# AQ_Schematic.net
KiCad netlist of a schematic drawn in Altium Designer
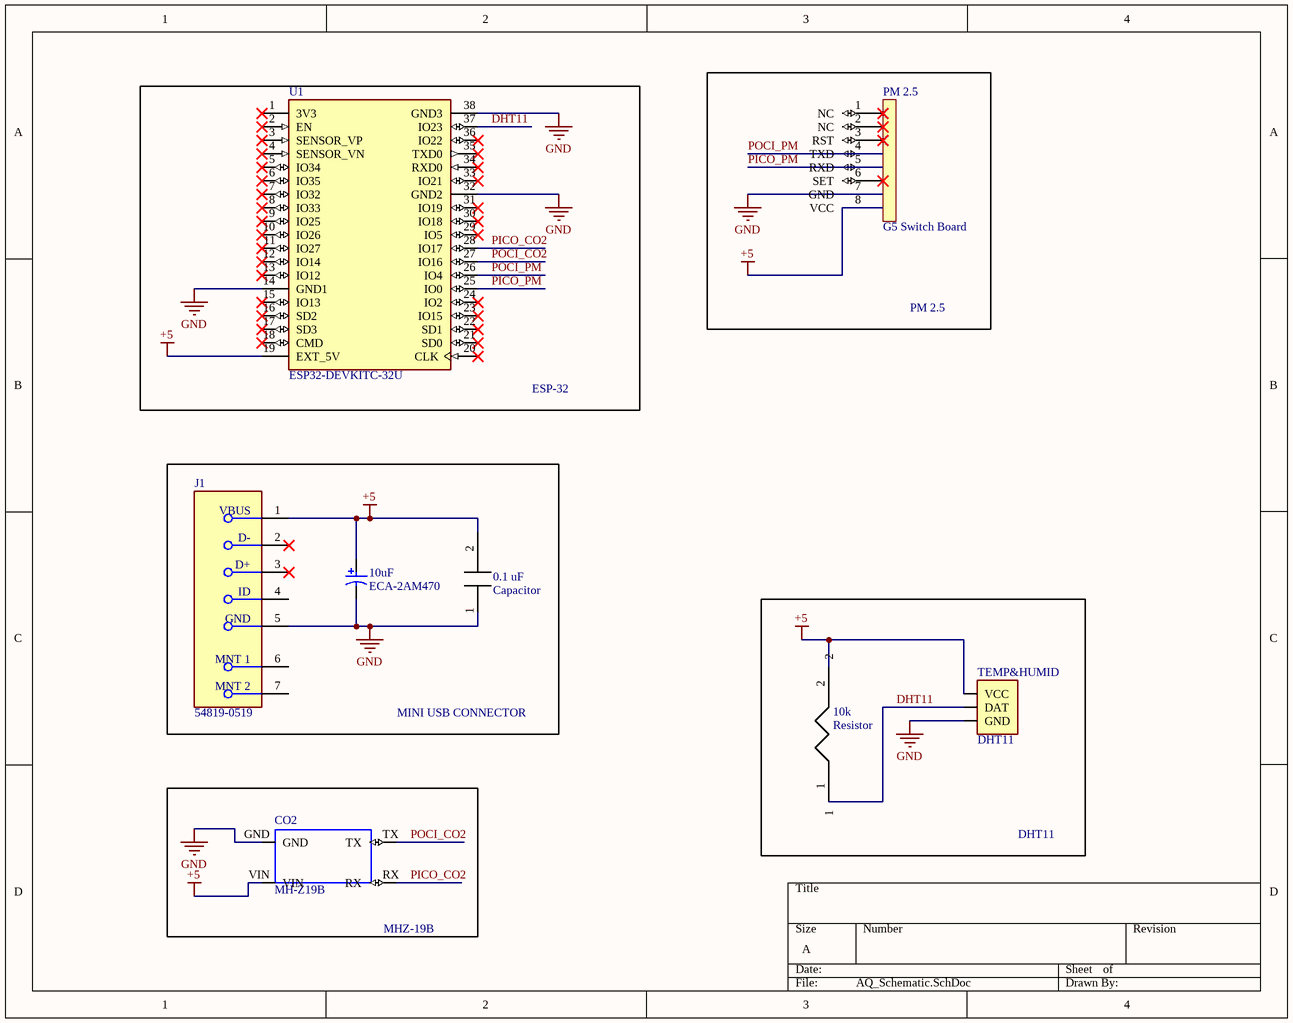
[diagram p0: AQ_Schematic.SchDoc]

(export (version "E")
  (design (tool "Eeschema 10.0.6"))
  (components
    (comp (ref "0.1 uF")
      (value "Capacitor")
      (footprint "PCBComponent_1")
      (libsource (lib "Capacitor") (part "Capacitor"))
    )
    (comp (ref "10k")
      (value "Resistor")
      (footprint "Resistor")
      (libsource (lib "Resistor") (part "Resistor"))
    )
    (comp (ref "10uF")
      (value "ECA-2AM470")
      (footprint "CAPPR65-350-1150X800X1250")
      (description "Aluminum Electrolytic Capacitor, 47 uF, +/- 20%, 100 V, -40 to 85 degC, 2-Pin THD, RoHS, Bulk")
      (libsource (lib "Components - 19.07.24 - 18.26") (part "CMP-1665-00041-1"))
    )
    (comp (ref "CO2")
      (value "MH-Z19B")
      (footprint "MH-Z19B-FOOT:MH-Z19B-FOOT")
      (description "Intelligent Infrared CO2 Module")
      (fields (field (name "MF") "Winsen"))
      (libsource (lib "MH-Z19B") (part "MH-Z19B"))
    )
    (comp (ref "J1")
      (value "54819-0519")
      (footprint "FP-54819-0519-MFG")
      (description "CONN RCPT USB2.0 MINI B 5P R/A")
      (libsource (lib "Components - 19.07.24 - 18.14") (part "CMP-04767-000009-1"))
    )
    (comp (ref "PM 2.5")
      (value "G5 Switch Board")
      (footprint "PM2.5")
      (libsource (lib "G5_Connector") (part "G5 Switch Board"))
    )
    (comp (ref "TEMP&HUMID")
      (value "DHT11")
      (footprint "SENSOR-DHT11")
      (description "Humidity, Temperature Digital Â±5% RH Through Hole")
      (fields (field (name "MF") "UNIVERSAL-SOLDER Electronics Ltd"))
      (libsource (lib "DHT11") (part "DHT11"))
    )
    (comp (ref "U1")
      (value "ESP32-DEVKITC-32U")
      (footprint "MODULE_ESP32-DEVKITC-32U")
      (fields (field (name "MF") "Espressif Systems"))
      (libsource (lib "ESP32-DEVKITC-32U") (part "ESP32-DEVKITC-32U"))
    )
  )
  (nets
    (net (code "1") (name "+5") (class "Default")
      (node (ref "10uF") (pin "1") (pinfunction "1_1") (pintype "passive"))
      (node (ref "CO2") (pin "VIN") (pinfunction "VIN_VIN") (pintype "power_in"))
      (node (ref "J1") (pin "1") (pinfunction "VBUS_1") (pintype "power_in"))
      (node (ref "PM 2.5") (pin "8") (pinfunction "VCC_8") (pintype "power_in"))
      (node (ref "TEMP&HUMID") (pin "P$1") (pinfunction "VCC_P$1") (pintype "power_in"))
      (node (ref "U1") (pin "19") (pinfunction "EXT_5V_19") (pintype "power_in"))
    )
    (net (code "2") (name "/DHT11") (class "Default")
      (node (ref "TEMP&HUMID") (pin "P$2") (pinfunction "DAT_P$2") (pintype "bidirectional"))
      (node (ref "U1") (pin "37") (pinfunction "IO23_37") (pintype "bidirectional"))
    )
    (net (code "3") (name "/PICO_CO2") (class "Default")
      (node (ref "CO2") (pin "RX") (pinfunction "RX_RX") (pintype "bidirectional"))
      (node (ref "U1") (pin "28") (pinfunction "IO17_28") (pintype "bidirectional"))
    )
    (net (code "4") (name "/PICO_PM") (class "Default")
      (node (ref "PM 2.5") (pin "5") (pinfunction "RXD_5") (pintype "bidirectional"))
      (node (ref "U1") (pin "25") (pinfunction "IO0_25") (pintype "bidirectional"))
    )
    (net (code "5") (name "/POCI_CO2") (class "Default")
      (node (ref "CO2") (pin "TX") (pinfunction "TX_TX") (pintype "bidirectional"))
      (node (ref "U1") (pin "27") (pinfunction "IO16_27") (pintype "bidirectional"))
    )
    (net (code "6") (name "/POCI_PM") (class "Default")
      (node (ref "PM 2.5") (pin "4") (pinfunction "TXD_4") (pintype "bidirectional"))
      (node (ref "U1") (pin "26") (pinfunction "IO4_26") (pintype "bidirectional"))
    )
    (net (code "7") (name "GND") (class "Default")
      (node (ref "10uF") (pin "2") (pinfunction "2_2") (pintype "passive"))
      (node (ref "CO2") (pin "GND") (pinfunction "GND_GND") (pintype "power_in"))
      (node (ref "J1") (pin "5") (pinfunction "GND_5") (pintype "power_in"))
      (node (ref "PM 2.5") (pin "7") (pinfunction "GND_7") (pintype "power_in"))
      (node (ref "TEMP&HUMID") (pin "P$4") (pinfunction "GND_P$4") (pintype "power_in"))
      (node (ref "U1") (pin "14") (pinfunction "GND1_14") (pintype "power_in"))
      (node (ref "U1") (pin "32") (pinfunction "GND2_32") (pintype "power_in"))
      (node (ref "U1") (pin "38") (pinfunction "GND3_38") (pintype "power_in"))
    )
    (net (code "8") (name "unconnected-(0.1 uF-Pad1)") (class "Default")
      (node (ref "0.1 uF") (pin "1") (pintype "passive"))
    )
    (net (code "9") (name "unconnected-(0.1 uF-Pad2)") (class "Default")
      (node (ref "0.1 uF") (pin "2") (pintype "passive"))
    )
    (net (code "10") (name "unconnected-(10k-Pad1)") (class "Default")
      (node (ref "10k") (pin "1") (pinfunction "1_1") (pintype "passive"))
    )
    (net (code "11") (name "unconnected-(10k-Pad2)") (class "Default")
      (node (ref "10k") (pin "2") (pinfunction "2_2") (pintype "passive"))
    )
    (net (code "12") (name "unconnected-(J1-D+-Pad3)") (class "Default")
      (node (ref "J1") (pin "3") (pinfunction "D+_3") (pintype "passive+no_connect"))
    )
    (net (code "13") (name "unconnected-(J1-D--Pad2)") (class "Default")
      (node (ref "J1") (pin "2") (pinfunction "D-_2") (pintype "passive+no_connect"))
    )
    (net (code "14") (name "unconnected-(J1-ID-Pad4)") (class "Default")
      (node (ref "J1") (pin "4") (pinfunction "ID_4") (pintype "passive"))
    )
    (net (code "15") (name "unconnected-(J1-MNT_1-Pad6)") (class "Default")
      (node (ref "J1") (pin "6") (pinfunction "MNT_1_6") (pintype "passive"))
    )
    (net (code "16") (name "unconnected-(J1-MNT_2-Pad7)") (class "Default")
      (node (ref "J1") (pin "7") (pinfunction "MNT_2_7") (pintype "passive"))
    )
    (net (code "17") (name "unconnected-(PM 2.5-NC-Pad1)") (class "Default")
      (node (ref "PM 2.5") (pin "1") (pinfunction "NC_1") (pintype "bidirectional+no_connect"))
    )
    (net (code "18") (name "unconnected-(PM 2.5-NC-Pad2)") (class "Default")
      (node (ref "PM 2.5") (pin "2") (pinfunction "NC_2") (pintype "bidirectional+no_connect"))
    )
    (net (code "19") (name "unconnected-(PM 2.5-RST-Pad3)") (class "Default")
      (node (ref "PM 2.5") (pin "3") (pinfunction "RST_3") (pintype "bidirectional+no_connect"))
    )
    (net (code "20") (name "unconnected-(PM 2.5-SET-Pad6)") (class "Default")
      (node (ref "PM 2.5") (pin "6") (pinfunction "SET_6") (pintype "bidirectional+no_connect"))
    )
    (net (code "21") (name "unconnected-(U1-3V3-Pad1)") (class "Default")
      (node (ref "U1") (pin "1") (pinfunction "3V3_1") (pintype "power_in+no_connect"))
    )
    (net (code "22") (name "unconnected-(U1-CLK-Pad20)") (class "Default")
      (node (ref "U1") (pin "20") (pinfunction "CLK_20") (pintype "input+no_connect"))
    )
    (net (code "23") (name "unconnected-(U1-CMD-Pad18)") (class "Default")
      (node (ref "U1") (pin "18") (pinfunction "CMD_18") (pintype "bidirectional+no_connect"))
    )
    (net (code "24") (name "unconnected-(U1-EN-Pad2)") (class "Default")
      (node (ref "U1") (pin "2") (pinfunction "EN_2") (pintype "input+no_connect"))
    )
    (net (code "25") (name "unconnected-(U1-IO2-Pad24)") (class "Default")
      (node (ref "U1") (pin "24") (pinfunction "IO2_24") (pintype "bidirectional+no_connect"))
    )
    (net (code "26") (name "unconnected-(U1-IO5-Pad29)") (class "Default")
      (node (ref "U1") (pin "29") (pinfunction "IO5_29") (pintype "bidirectional+no_connect"))
    )
    (net (code "27") (name "unconnected-(U1-IO12-Pad13)") (class "Default")
      (node (ref "U1") (pin "13") (pinfunction "IO12_13") (pintype "bidirectional+no_connect"))
    )
    (net (code "28") (name "unconnected-(U1-IO13-Pad15)") (class "Default")
      (node (ref "U1") (pin "15") (pinfunction "IO13_15") (pintype "bidirectional+no_connect"))
    )
    (net (code "29") (name "unconnected-(U1-IO14-Pad12)") (class "Default")
      (node (ref "U1") (pin "12") (pinfunction "IO14_12") (pintype "bidirectional+no_connect"))
    )
    (net (code "30") (name "unconnected-(U1-IO15-Pad23)") (class "Default")
      (node (ref "U1") (pin "23") (pinfunction "IO15_23") (pintype "bidirectional+no_connect"))
    )
    (net (code "31") (name "unconnected-(U1-IO18-Pad30)") (class "Default")
      (node (ref "U1") (pin "30") (pinfunction "IO18_30") (pintype "bidirectional+no_connect"))
    )
    (net (code "32") (name "unconnected-(U1-IO19-Pad31)") (class "Default")
      (node (ref "U1") (pin "31") (pinfunction "IO19_31") (pintype "bidirectional+no_connect"))
    )
    (net (code "33") (name "unconnected-(U1-IO21-Pad33)") (class "Default")
      (node (ref "U1") (pin "33") (pinfunction "IO21_33") (pintype "bidirectional+no_connect"))
    )
    (net (code "34") (name "unconnected-(U1-IO22-Pad36)") (class "Default")
      (node (ref "U1") (pin "36") (pinfunction "IO22_36") (pintype "bidirectional+no_connect"))
    )
    (net (code "35") (name "unconnected-(U1-IO25-Pad9)") (class "Default")
      (node (ref "U1") (pin "9") (pinfunction "IO25_9") (pintype "bidirectional+no_connect"))
    )
    (net (code "36") (name "unconnected-(U1-IO26-Pad10)") (class "Default")
      (node (ref "U1") (pin "10") (pinfunction "IO26_10") (pintype "bidirectional+no_connect"))
    )
    (net (code "37") (name "unconnected-(U1-IO27-Pad11)") (class "Default")
      (node (ref "U1") (pin "11") (pinfunction "IO27_11") (pintype "bidirectional+no_connect"))
    )
    (net (code "38") (name "unconnected-(U1-IO32-Pad7)") (class "Default")
      (node (ref "U1") (pin "7") (pinfunction "IO32_7") (pintype "bidirectional+no_connect"))
    )
    (net (code "39") (name "unconnected-(U1-IO33-Pad8)") (class "Default")
      (node (ref "U1") (pin "8") (pinfunction "IO33_8") (pintype "bidirectional+no_connect"))
    )
    (net (code "40") (name "unconnected-(U1-IO34-Pad5)") (class "Default")
      (node (ref "U1") (pin "5") (pinfunction "IO34_5") (pintype "bidirectional+no_connect"))
    )
    (net (code "41") (name "unconnected-(U1-IO35-Pad6)") (class "Default")
      (node (ref "U1") (pin "6") (pinfunction "IO35_6") (pintype "bidirectional+no_connect"))
    )
    (net (code "42") (name "unconnected-(U1-RXD0-Pad34)") (class "Default")
      (node (ref "U1") (pin "34") (pinfunction "RXD0_34") (pintype "input+no_connect"))
    )
    (net (code "43") (name "unconnected-(U1-SD0-Pad21)") (class "Default")
      (node (ref "U1") (pin "21") (pinfunction "SD0_21") (pintype "bidirectional+no_connect"))
    )
    (net (code "44") (name "unconnected-(U1-SD1-Pad22)") (class "Default")
      (node (ref "U1") (pin "22") (pinfunction "SD1_22") (pintype "bidirectional+no_connect"))
    )
    (net (code "45") (name "unconnected-(U1-SD2-Pad16)") (class "Default")
      (node (ref "U1") (pin "16") (pinfunction "SD2_16") (pintype "bidirectional+no_connect"))
    )
    (net (code "46") (name "unconnected-(U1-SD3-Pad17)") (class "Default")
      (node (ref "U1") (pin "17") (pinfunction "SD3_17") (pintype "bidirectional+no_connect"))
    )
    (net (code "47") (name "unconnected-(U1-SENSOR_VN-Pad4)") (class "Default")
      (node (ref "U1") (pin "4") (pinfunction "SENSOR_VN_4") (pintype "input+no_connect"))
    )
    (net (code "48") (name "unconnected-(U1-SENSOR_VP-Pad3)") (class "Default")
      (node (ref "U1") (pin "3") (pinfunction "SENSOR_VP_3") (pintype "input+no_connect"))
    )
    (net (code "49") (name "unconnected-(U1-TXD0-Pad35)") (class "Default")
      (node (ref "U1") (pin "35") (pinfunction "TXD0_35") (pintype "output+no_connect"))
    )
  )
)
